# 7_High_Voltage.net
KiCad netlist of a schematic drawn in Altium Designer
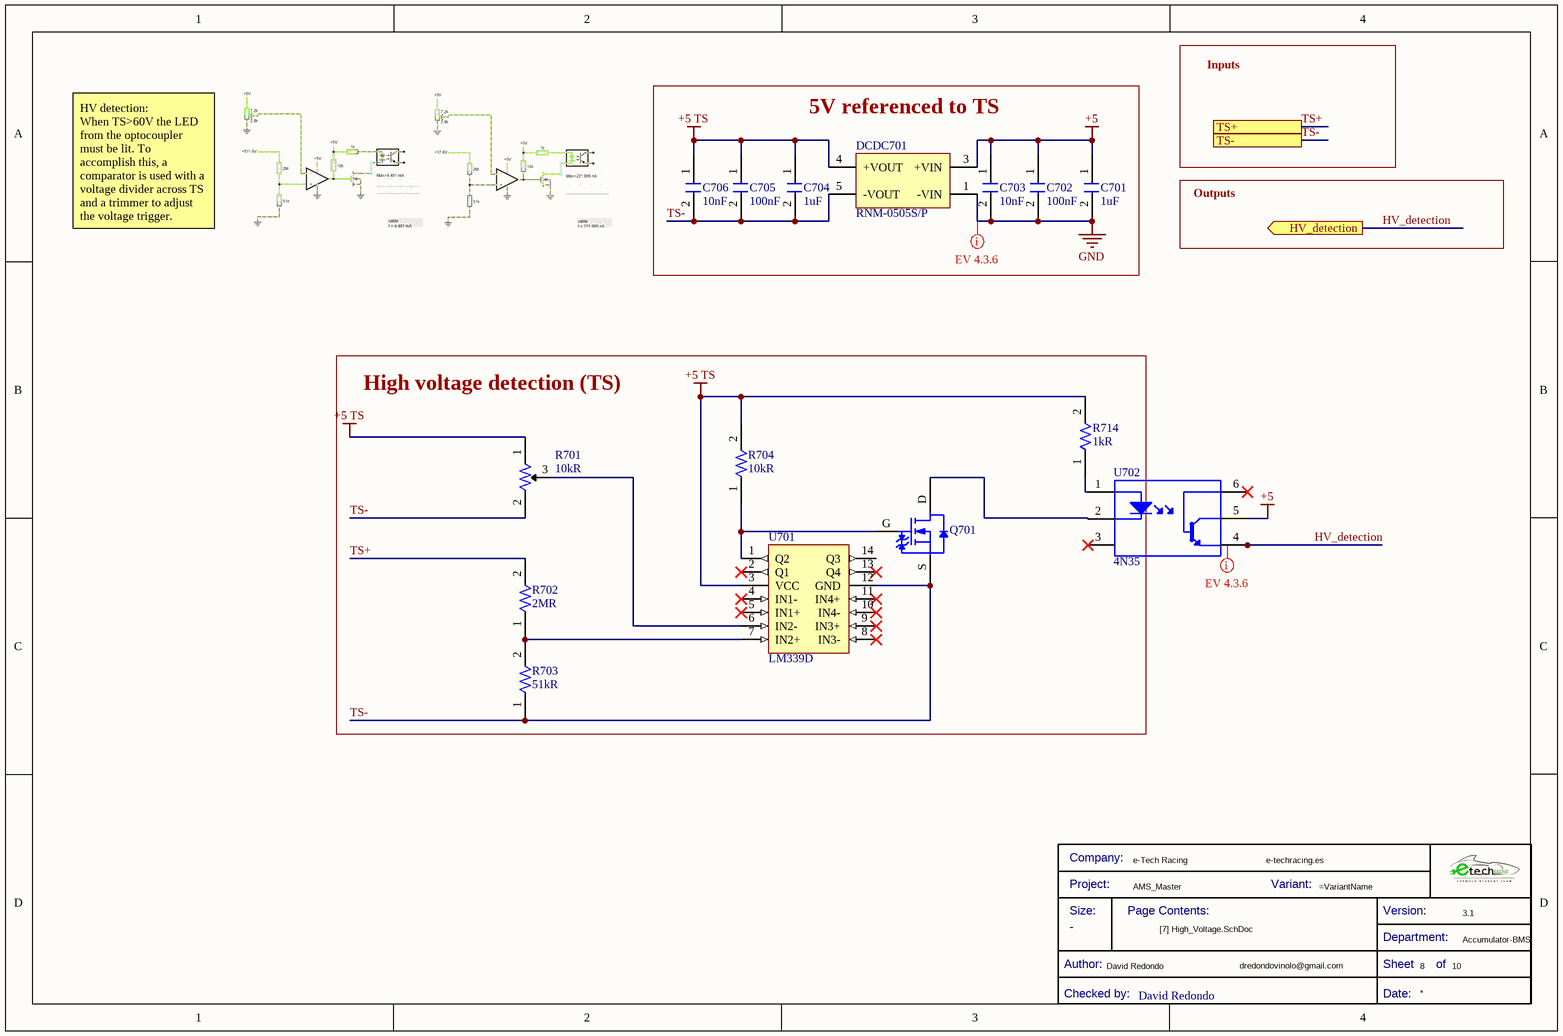
[diagram p0: [7] High_Voltage.SchDoc]

(export (version "E")
  (design (tool "Eeschema 10.0.6"))
  (components
    (comp (ref "C701")
      (value "885012207103")
      (footprint "C0805FNPC-R")
      (fields
        (field (name "TOLERANCE") "10%")
        (field (name "CAPACITANCE") "1uF")
        (field (name ".CREATOR") "GP")
      )
      (libsource (lib "Passives") (part "C1u-50V-0805FNPC-X7R"))
    )
    (comp (ref "C702")
      (value "885012207098")
      (footprint "C0805FNPC-R")
      (description "Cap, 0.1ΜF, 50V, 10%, X7R, 0805")
      (fields
        (field (name "TOLERANCE") "10%")
        (field (name "CAPACITANCE") "100nF")
        (field (name ".CREATOR") "DR")
      )
      (libsource (lib "Passives") (part "C100n-50V-0805FNPC-X7R"))
    )
    (comp (ref "C703")
      (value "885012207092")
      (footprint "C0805FNPC-R")
      (description "Cap, 0.01ΜF, 50V, 10%, X7R, 0805")
      (fields
        (field (name "TOLERANCE") "10%")
        (field (name "CAPACITANCE") "10nF")
        (field (name ".CREATOR") "DR")
      )
      (libsource (lib "Passives") (part "C10n-50V-0805FNPC-X7R"))
    )
    (comp (ref "C704")
      (value "885012207103")
      (footprint "C0805FNPC-R")
      (fields
        (field (name "TOLERANCE") "10%")
        (field (name "CAPACITANCE") "1uF")
        (field (name ".CREATOR") "GP")
      )
      (libsource (lib "Passives") (part "C1u-50V-0805FNPC-X7R"))
    )
    (comp (ref "C705")
      (value "885012207098")
      (footprint "C0805FNPC-R")
      (description "Cap, 0.1ΜF, 50V, 10%, X7R, 0805")
      (fields
        (field (name "TOLERANCE") "10%")
        (field (name "CAPACITANCE") "100nF")
        (field (name ".CREATOR") "DR")
      )
      (libsource (lib "Passives") (part "C100n-50V-0805FNPC-X7R"))
    )
    (comp (ref "C706")
      (value "885012207092")
      (footprint "C0805FNPC-R")
      (description "Cap, 0.01ΜF, 50V, 10%, X7R, 0805")
      (fields
        (field (name "TOLERANCE") "10%")
        (field (name "CAPACITANCE") "10nF")
        (field (name ".CREATOR") "DR")
      )
      (libsource (lib "Passives") (part "C10n-50V-0805FNPC-X7R"))
    )
    (comp (ref "DCDC701")
      (value "RNM-0505S/P")
      (footprint "DCDC_RNM-XX05S/P")
      (description "1W DC/DC-Converter 'ECONOLINE' DIP6 1kV unreg; V. In: 05; V. Out: 05; mA. Out: 200")
      (fields
        (field (name "MANUFACTURER") "Recom")
        (field (name "MANUFACTURER PART NUMBER") "RNM-0505S/P")
        (field (name ".CREATOR") "GP")
      )
      (libsource (lib "Semiconductor") (part "DCDC_RNM-0505S/P"))
    )
    (comp (ref "Q701")
      (value "SQ2318BES-T1_GE3")
      (footprint "TRT-NCH-3/35-CPH")
      (description "Automotive N-channel 40 V (d-s) 175C Mosfet SOT-23")
      (fields (field (name ".CREATOR") "DO"))
      (libsource (lib "Semiconductor") (part "TRT-NCH-8/40-SQ"))
    )
    (comp (ref "R701")
      (value "3296W-1-103LF")
      (footprint "R10k-VTR")
      (description "Trimmer, Cermet, Rest 10 Kilohms, PCB, 25 Turns, Pwr-Rtg 0.5W, 3296 Series")
      (fields
        (field (name "MANUFACTURER") "Bourns")
        (field (name "TOLERANCE") "10%")
        (field (name "RESISTANCE") "10kR")
        (field (name ".CREATOR") "DO")
      )
      (libsource (lib "Passives") (part "R10k-VTR"))
    )
    (comp (ref "R702")
      (value "R2M-2512FTK")
      (footprint "R2512FTK")
      (description "Current Sense Resistors - SMD 3watts .002ohms 1%")
      (fields
        (field (name "MANUFACTURER") "Vishay Dale")
        (field (name "MANUFACTURER PART NUMBER") "WSLP25122L000FEA")
        (field (name "RESISTANCE") "2MR")
      )
      (libsource (lib "Passives") (part "R2M-2512FTK"))
    )
    (comp (ref "R703")
      (value "CRCW120610K0FKEA")
      (footprint "R1206FTK-W")
      (description "Res Thick Film 1206 51K Ohm 1% 1/4W ±100ppm/°C Molded SMD SMD Punched Carrier T/R")
      (fields
        (field (name "MANUFACTURER") "Panasonic")
        (field (name "MANUFACTURER PART NUMBER") "ERJ-S08F5102V")
        (field (name "RESISTANCE") "51kR")
        (field (name ".CREATOR") "DO")
      )
      (libsource (lib "Passives") (part "R51k-1206FTK"))
    )
    (comp (ref "R704")
      (value "CR0805-JW-103ELF")
      (footprint "R0805FTK")
      (fields
        (field (name "TOLERANCE") "5%")
        (field (name "RESISTANCE") "10kR")
        (field (name ".CREATOR") "DR")
      )
      (libsource (lib "Passives") (part "R10k-0805FTK"))
    )
    (comp (ref "R714")
      (value "CR0805-JW-102ELF")
      (footprint "R0805FTK")
      (description "Res Thick Film 0805 1K Ohm 5% 1/8W ±200ppm/°C Molded SMD SMD Paper Tape on Plastic Reel")
      (fields
        (field (name "TOLERANCE") "5%")
        (field (name "RESISTANCE") "1kR")
        (field (name ".CREATOR") "GP")
      )
      (libsource (lib "Passives") (part "R1k-0805FTK"))
    )
    (comp (ref "U701")
      (value "LM339D")
      (footprint "Array_4_Amp_LM339D")
      (description "Comparator Quad ±18V/36V 14-Pin SOIC Tube")
      (fields
        (field (name "MANUFACTURER") "Texas Instruments")
        (field (name "MANUFACTURER PART NUMBER") "LM339D")
        (field (name ".CREATOR") "DO")
      )
      (libsource (lib "Integrated circuits") (part "Array_4_Amp_LM339D"))
    )
    (comp (ref "U702")
      (value "4N35")
      (footprint "Optocoupler_4N35")
      (description "Optocoupler DC-IN 1-CH Transistor With Base DC-OUT 6-Pin PDIP SMD T/R")
      (fields
        (field (name "MANUFACTURER") "Vishay Lite-On")
        (field (name "MANUFACTURER PART NUMBER") "CNY17-4S-TA1")
        (field (name ".CREATOR") "DO")
      )
      (libsource (lib "Semiconductor") (part "Optocoupler_4N35"))
    )
  )
  (nets
    (net (code "1") (name "+5") (class "Default")
      (node (ref "C701") (pin "1") (pinfunction "1_1") (pintype "passive"))
      (node (ref "C702") (pin "1") (pinfunction "1_1") (pintype "passive"))
      (node (ref "C703") (pin "1") (pinfunction "1_1") (pintype "passive"))
      (node (ref "DCDC701") (pin "3") (pinfunction "+VIN_3") (pintype "passive"))
      (node (ref "U702") (pin "5") (pinfunction "E_5") (pintype "passive"))
    )
    (net (code "2") (name "+5 TS") (class "Default")
      (node (ref "C704") (pin "1") (pinfunction "1_1") (pintype "passive"))
      (node (ref "C705") (pin "1") (pinfunction "1_1") (pintype "passive"))
      (node (ref "C706") (pin "1") (pinfunction "1_1") (pintype "passive"))
      (node (ref "DCDC701") (pin "4") (pinfunction "+VOUT_4") (pintype "passive"))
      (node (ref "R701") (pin "1") (pinfunction "2_1") (pintype "passive"))
      (node (ref "R704") (pin "2") (pinfunction "2_2") (pintype "passive"))
      (node (ref "R714") (pin "2") (pinfunction "2_2") (pintype "passive"))
      (node (ref "U701") (pin "3") (pinfunction "VCC_3") (pintype "power_in"))
    )
    (net (code "3") (name "/HV_detection") (class "Default")
      (node (ref "U702") (pin "4") (pinfunction "E_4") (pintype "passive"))
    )
    (net (code "4") (name "/TS+") (class "Default")
      (node (ref "R702") (pin "2") (pinfunction "2_2") (pintype "passive"))
    )
    (net (code "5") (name "/TS-") (class "Default")
      (node (ref "C704") (pin "2") (pinfunction "2_2") (pintype "passive"))
      (node (ref "C705") (pin "2") (pinfunction "2_2") (pintype "passive"))
      (node (ref "C706") (pin "2") (pinfunction "2_2") (pintype "passive"))
      (node (ref "DCDC701") (pin "5") (pinfunction "-VOUT_5") (pintype "passive"))
      (node (ref "Q701") (pin "S") (pinfunction "S_S") (pintype "passive"))
      (node (ref "R701") (pin "2") (pinfunction "2_2") (pintype "passive"))
      (node (ref "R703") (pin "1") (pinfunction "1_1") (pintype "passive"))
      (node (ref "U701") (pin "12") (pinfunction "GND_12") (pintype "power_in"))
    )
    (net (code "6") (name "GND") (class "Default")
      (node (ref "C701") (pin "2") (pinfunction "2_2") (pintype "passive"))
      (node (ref "C702") (pin "2") (pinfunction "2_2") (pintype "passive"))
      (node (ref "C703") (pin "2") (pinfunction "2_2") (pintype "passive"))
      (node (ref "DCDC701") (pin "1") (pinfunction "-VIN_1") (pintype "passive"))
    )
    (net (code "7") (name "Net-(U701-IN2+)") (class "Default")
      (node (ref "R702") (pin "1") (pinfunction "1_1") (pintype "passive"))
      (node (ref "R703") (pin "2") (pinfunction "2_2") (pintype "passive"))
      (node (ref "U701") (pin "7") (pinfunction "IN2+_7") (pintype "input"))
    )
    (net (code "8") (name "Net-(U701-IN2-)") (class "Default")
      (node (ref "R701") (pin "3") (pinfunction "3_3") (pintype "passive"))
      (node (ref "U701") (pin "6") (pinfunction "IN2-_6") (pintype "input"))
    )
    (net (code "9") (name "Net-(U701-Q2)") (class "Default")
      (node (ref "Q701") (pin "G") (pinfunction "G_G") (pintype "passive"))
      (node (ref "R704") (pin "1") (pinfunction "1_1") (pintype "passive"))
      (node (ref "U701") (pin "1") (pinfunction "Q2_1") (pintype "output"))
    )
    (net (code "10") (name "Net-(U702-A)") (class "Default")
      (node (ref "R714") (pin "1") (pinfunction "1_1") (pintype "passive"))
      (node (ref "U702") (pin "1") (pinfunction "A_1") (pintype "passive"))
    )
    (net (code "11") (name "Net-(U702-K)") (class "Default")
      (node (ref "Q701") (pin "D") (pinfunction "D_D") (pintype "passive"))
      (node (ref "U702") (pin "2") (pinfunction "K_2") (pintype "passive"))
    )
    (net (code "12") (name "unconnected-(U701-IN1+-Pad5)") (class "Default")
      (node (ref "U701") (pin "5") (pinfunction "IN1+_5") (pintype "input+no_connect"))
    )
    (net (code "13") (name "unconnected-(U701-IN1--Pad4)") (class "Default")
      (node (ref "U701") (pin "4") (pinfunction "IN1-_4") (pintype "input+no_connect"))
    )
    (net (code "14") (name "unconnected-(U701-IN3+-Pad9)") (class "Default")
      (node (ref "U701") (pin "9") (pinfunction "IN3+_9") (pintype "input+no_connect"))
    )
    (net (code "15") (name "unconnected-(U701-IN3--Pad8)") (class "Default")
      (node (ref "U701") (pin "8") (pinfunction "IN3-_8") (pintype "input+no_connect"))
    )
    (net (code "16") (name "unconnected-(U701-IN4+-Pad11)") (class "Default")
      (node (ref "U701") (pin "11") (pinfunction "IN4+_11") (pintype "input+no_connect"))
    )
    (net (code "17") (name "unconnected-(U701-IN4--Pad10)") (class "Default")
      (node (ref "U701") (pin "10") (pinfunction "IN4-_10") (pintype "input+no_connect"))
    )
    (net (code "18") (name "unconnected-(U701-Q1-Pad2)") (class "Default")
      (node (ref "U701") (pin "2") (pinfunction "Q1_2") (pintype "output+no_connect"))
    )
    (net (code "19") (name "unconnected-(U701-Q3-Pad14)") (class "Default")
      (node (ref "U701") (pin "14") (pinfunction "Q3_14") (pintype "output"))
    )
    (net (code "20") (name "unconnected-(U701-Q4-Pad13)") (class "Default")
      (node (ref "U701") (pin "13") (pinfunction "Q4_13") (pintype "output+no_connect"))
    )
    (net (code "21") (name "unconnected-(U702-C-Pad3)") (class "Default")
      (node (ref "U702") (pin "3") (pinfunction "C_3") (pintype "passive+no_connect"))
    )
    (net (code "22") (name "unconnected-(U702-E-Pad6)") (class "Default")
      (node (ref "U702") (pin "6") (pinfunction "E_6") (pintype "passive+no_connect"))
    )
  )
)
